# RS232.net
KiCad netlist of a schematic drawn in Altium Designer
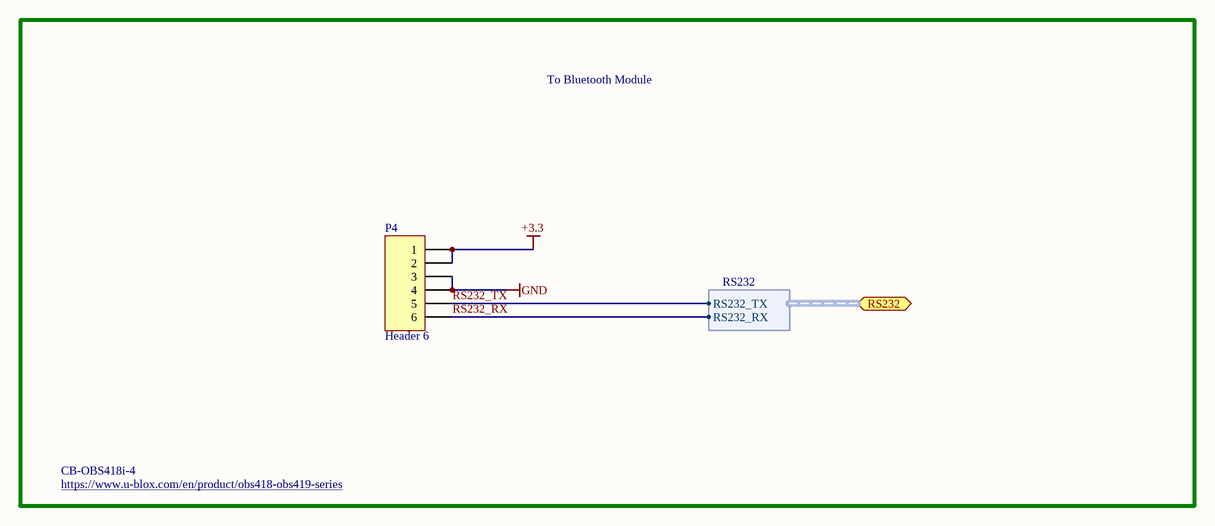
[diagram p0: RS232.SchDoc]

(export (version "E")
  (design (tool "Eeschema 10.0.6"))
  (components
    (comp (ref "P4")
      (value "Header 6")
      (footprint "HDR1X6")
      (description "Header, 6-Pin")
      (fields (field (name "PUBLISHER") "Altium Limited"))
      (libsource (lib "Miscellaneous Connectors") (part "Header 6"))
    )
  )
  (nets
    (net (code "2") (name "+3.3") (class "Default")
      (node (ref "P4") (pin "1") (pinfunction "1_1") (pintype "passive"))
      (node (ref "P4") (pin "2") (pinfunction "2_2") (pintype "passive"))
    )
    (net (code "3") (name "/RS232_RX") (class "Default")
      (node (ref "P4") (pin "6") (pinfunction "6_6") (pintype "passive"))
    )
    (net (code "4") (name "/RS232_TX") (class "Default")
      (node (ref "P4") (pin "5") (pinfunction "5_5") (pintype "passive"))
    )
    (net (code "6") (name "GND") (class "Default")
      (node (ref "P4") (pin "3") (pinfunction "3_3") (pintype "passive"))
      (node (ref "P4") (pin "4") (pinfunction "4_4") (pintype "passive"))
    )
  )
)
